# 04_MCU_ESP32.net
KiCad netlist of a schematic drawn in Altium Designer
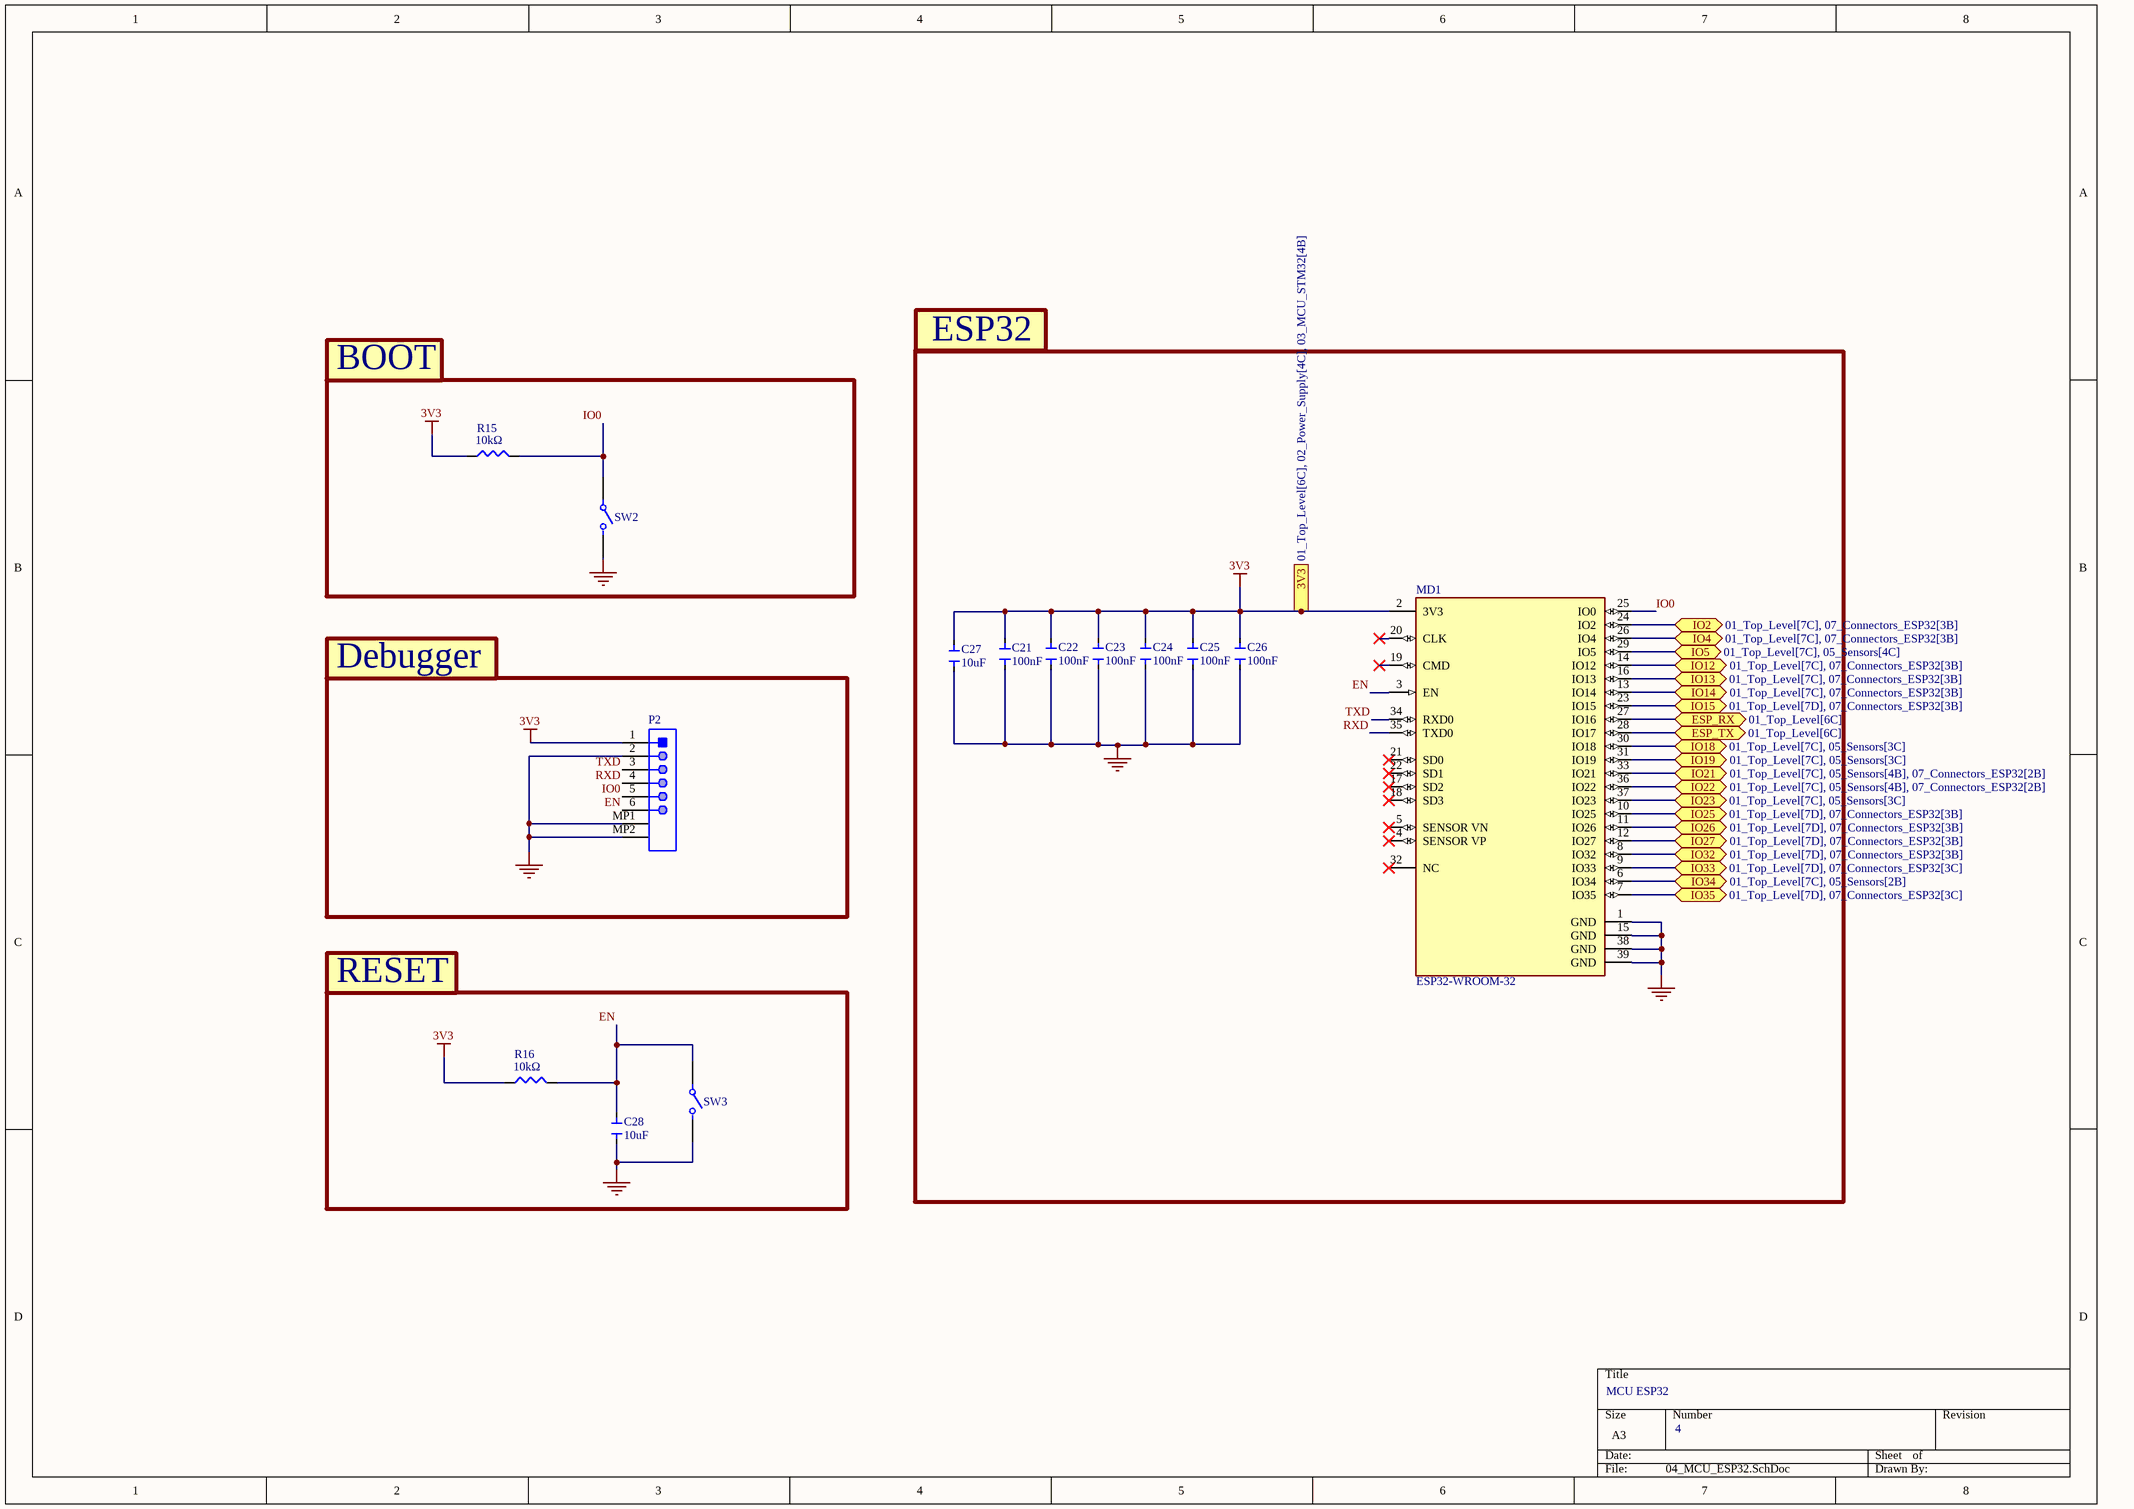
[diagram p0: 04_MCU_ESP32.SchDoc]

(export (version "E")
  (design (tool "Eeschema 10.0.6"))
  (components
    (comp (ref "C21")
      (value "100nF")
      (footprint "CAP_100nF")
      (description "CAP 100nF 50V X7R ±10% 0603 Ceramic Capacitors RoHS")
      (fields
        (field (name "MANUFACTURER") "YAGEO")
        (field (name "MANUFACTURER PART NUMBER") "CC0603KRX7R9BB104")
      )
      (libsource (lib "Components_Schlib") (part "CAP_100nF"))
    )
    (comp (ref "C22")
      (value "100nF")
      (footprint "CAP_100nF")
      (description "CAP 100nF 50V X7R ±10% 0603 Ceramic Capacitors RoHS")
      (fields
        (field (name "MANUFACTURER") "YAGEO")
        (field (name "MANUFACTURER PART NUMBER") "CC0603KRX7R9BB104")
      )
      (libsource (lib "Components_Schlib") (part "CAP_100nF"))
    )
    (comp (ref "C23")
      (value "100nF")
      (footprint "CAP_100nF")
      (description "CAP 100nF 50V X7R ±10% 0603 Ceramic Capacitors RoHS")
      (fields
        (field (name "MANUFACTURER") "YAGEO")
        (field (name "MANUFACTURER PART NUMBER") "CC0603KRX7R9BB104")
      )
      (libsource (lib "Components_Schlib") (part "CAP_100nF"))
    )
    (comp (ref "C24")
      (value "100nF")
      (footprint "CAP_100nF")
      (description "CAP 100nF 50V X7R ±10% 0603 Ceramic Capacitors RoHS")
      (fields
        (field (name "MANUFACTURER") "YAGEO")
        (field (name "MANUFACTURER PART NUMBER") "CC0603KRX7R9BB104")
      )
      (libsource (lib "Components_Schlib") (part "CAP_100nF"))
    )
    (comp (ref "C25")
      (value "100nF")
      (footprint "CAP_100nF")
      (description "CAP 100nF 50V X7R ±10% 0603 Ceramic Capacitors RoHS")
      (fields
        (field (name "MANUFACTURER") "YAGEO")
        (field (name "MANUFACTURER PART NUMBER") "CC0603KRX7R9BB104")
      )
      (libsource (lib "Components_Schlib") (part "CAP_100nF"))
    )
    (comp (ref "C26")
      (value "100nF")
      (footprint "CAP_100nF")
      (description "CAP 100nF 50V X7R ±10% 0603 Ceramic Capacitors RoHS")
      (fields
        (field (name "MANUFACTURER") "YAGEO")
        (field (name "MANUFACTURER PART NUMBER") "CC0603KRX7R9BB104")
      )
      (libsource (lib "Components_Schlib") (part "CAP_100nF"))
    )
    (comp (ref "C27")
      (value "10uF")
      (footprint "CAP_10uF")
      (description "CAP CER 10UF 10V X5R 0402")
      (fields
        (field (name "MANUFACTURER") "Samsung Electro-Mechanics")
        (field (name "MANUFACTURER PART NUMBER") "C307415")
      )
      (libsource (lib "Components_Schlib") (part "CAP_0402_10UF"))
    )
    (comp (ref "C28")
      (value "10uF")
      (footprint "CAP_10uF")
      (description "CAP CER 10UF 10V X5R 0402")
      (fields
        (field (name "MANUFACTURER") "Samsung Electro-Mechanics")
        (field (name "MANUFACTURER PART NUMBER") "C307415")
      )
      (libsource (lib "Components_Schlib") (part "CAP_0402_10UF"))
    )
    (comp (ref "MD1")
      (value "ESP32-WROOM-32")
      (footprint "FP-ESP32-WROOM-32-MFG")
      (description "RX TXRX MOD WIFI SURFACE MOUNT")
      (libsource (lib "Altium Content Vault") (part "ee866abf0b6c51247b7f5cdebf2f250"))
    )
    (comp (ref "P2")
      (value "SM06B-SRSS-TB(LF)(SN)")
      (footprint "JST-SM06B-SRSS-TB_V")
      (description "Male Header, Pitch 1 mm, 1 x 6 Position, Height 2.95 mm, -25 to 85 degC, RoHS, Tape and Reel")
      (fields (field (name "MANUFACTURER") "JST"))
      (libsource (lib "Altium Content Vault") (part "CN-1P-2M-R6"))
    )
    (comp (ref "R15")
      (value "10kΩ")
      (footprint "RES_10K")
      (description "100mW Thin Film Resistor ±0.1% ±10ppm/℃ 10kΩ 0603 Chip Resistor - Surface Mount ROHS")
      (fields
        (field (name "MANUFACTURER") "Yageo Group")
        (field (name "MANUFACTURER PART NUMBER") "RT0603BRB07169KL")
      )
      (libsource (lib "Components_Schlib") (part "RES_0603_10K"))
    )
    (comp (ref "R16")
      (value "10kΩ")
      (footprint "RES_10K")
      (description "100mW Thin Film Resistor ±0.1% ±10ppm/℃ 10kΩ 0603 Chip Resistor - Surface Mount ROHS")
      (fields
        (field (name "MANUFACTURER") "Yageo Group")
        (field (name "MANUFACTURER PART NUMBER") "RT0603BRB07169KL")
      )
      (libsource (lib "Components_Schlib") (part "RES_0603_10K"))
    )
    (comp (ref "SW2")
      (value "EVP-BD6C1A000")
      (footprint "FP-EVP-BD6C1A000-MFG")
      (description "EVP-BD6C1A000 Switch Tactile N.O. SPST Round Button J-Bend 0.05A 12VDC 3.5N SMD Automotive T/R")
      (libsource (lib "Altium Content Vault") (part "2b0b2b19372efd94fa7681498149756"))
    )
    (comp (ref "SW3")
      (value "EVP-BD6C1A000")
      (footprint "FP-EVP-BD6C1A000-MFG")
      (description "EVP-BD6C1A000 Switch Tactile N.O. SPST Round Button J-Bend 0.05A 12VDC 3.5N SMD Automotive T/R")
      (libsource (lib "Altium Content Vault") (part "2b0b2b19372efd94fa7681498149756"))
    )
  )
  (nets
    (net (code "1") (name "/EN") (class "Default")
      (node (ref "C28") (pin "1") (pinfunction "1_1") (pintype "passive"))
      (node (ref "MD1") (pin "3") (pinfunction "EN_3") (pintype "input"))
      (node (ref "P2") (pin "6") (pinfunction "6_6") (pintype "passive"))
      (node (ref "R16") (pin "2") (pinfunction "2_2") (pintype "passive"))
      (node (ref "SW3") (pin "A") (pinfunction "A_A") (pintype "passive"))
    )
    (net (code "2") (name "/ESP_RX") (class "Default")
      (node (ref "MD1") (pin "27") (pinfunction "IO16_27") (pintype "bidirectional"))
    )
    (net (code "3") (name "/ESP_TX") (class "Default")
      (node (ref "MD1") (pin "28") (pinfunction "IO17_28") (pintype "bidirectional"))
    )
    (net (code "4") (name "/IO0") (class "Default")
      (node (ref "MD1") (pin "25") (pinfunction "IO0_25") (pintype "bidirectional"))
      (node (ref "P2") (pin "5") (pinfunction "5_5") (pintype "passive"))
      (node (ref "R15") (pin "2") (pinfunction "2_2") (pintype "passive"))
      (node (ref "SW2") (pin "A") (pinfunction "A_A") (pintype "passive"))
    )
    (net (code "5") (name "/IO2") (class "Default")
      (node (ref "MD1") (pin "24") (pinfunction "IO2_24") (pintype "bidirectional"))
    )
    (net (code "6") (name "/IO4") (class "Default")
      (node (ref "MD1") (pin "26") (pinfunction "IO4_26") (pintype "bidirectional"))
    )
    (net (code "7") (name "/IO5") (class "Default")
      (node (ref "MD1") (pin "29") (pinfunction "IO5_29") (pintype "bidirectional"))
    )
    (net (code "8") (name "/IO12") (class "Default")
      (node (ref "MD1") (pin "14") (pinfunction "IO12_14") (pintype "bidirectional"))
    )
    (net (code "9") (name "/IO13") (class "Default")
      (node (ref "MD1") (pin "16") (pinfunction "IO13_16") (pintype "bidirectional"))
    )
    (net (code "10") (name "/IO14") (class "Default")
      (node (ref "MD1") (pin "13") (pinfunction "IO14_13") (pintype "bidirectional"))
    )
    (net (code "11") (name "/IO15") (class "Default")
      (node (ref "MD1") (pin "23") (pinfunction "IO15_23") (pintype "bidirectional"))
    )
    (net (code "12") (name "/IO18") (class "Default")
      (node (ref "MD1") (pin "30") (pinfunction "IO18_30") (pintype "bidirectional"))
    )
    (net (code "13") (name "/IO19") (class "Default")
      (node (ref "MD1") (pin "31") (pinfunction "IO19_31") (pintype "bidirectional"))
    )
    (net (code "14") (name "/IO21") (class "Default")
      (node (ref "MD1") (pin "33") (pinfunction "IO21_33") (pintype "bidirectional"))
    )
    (net (code "15") (name "/IO22") (class "Default")
      (node (ref "MD1") (pin "36") (pinfunction "IO22_36") (pintype "bidirectional"))
    )
    (net (code "16") (name "/IO23") (class "Default")
      (node (ref "MD1") (pin "37") (pinfunction "IO23_37") (pintype "bidirectional"))
    )
    (net (code "17") (name "/IO25") (class "Default")
      (node (ref "MD1") (pin "10") (pinfunction "IO25_10") (pintype "bidirectional"))
    )
    (net (code "18") (name "/IO26") (class "Default")
      (node (ref "MD1") (pin "11") (pinfunction "IO26_11") (pintype "bidirectional"))
    )
    (net (code "19") (name "/IO27") (class "Default")
      (node (ref "MD1") (pin "12") (pinfunction "IO27_12") (pintype "bidirectional"))
    )
    (net (code "20") (name "/IO32") (class "Default")
      (node (ref "MD1") (pin "8") (pinfunction "IO32_8") (pintype "bidirectional"))
    )
    (net (code "21") (name "/IO33") (class "Default")
      (node (ref "MD1") (pin "9") (pinfunction "IO33_9") (pintype "bidirectional"))
    )
    (net (code "22") (name "/IO34") (class "Default")
      (node (ref "MD1") (pin "6") (pinfunction "IO34_6") (pintype "bidirectional"))
    )
    (net (code "23") (name "/IO35") (class "Default")
      (node (ref "MD1") (pin "7") (pinfunction "IO35_7") (pintype "bidirectional"))
    )
    (net (code "24") (name "/RXD") (class "Default")
      (node (ref "MD1") (pin "35") (pinfunction "TXD0_35") (pintype "bidirectional"))
      (node (ref "P2") (pin "4") (pinfunction "4_4") (pintype "passive"))
    )
    (net (code "25") (name "/TXD") (class "Default")
      (node (ref "MD1") (pin "34") (pinfunction "RXD0_34") (pintype "bidirectional"))
      (node (ref "P2") (pin "3") (pinfunction "3_3") (pintype "passive"))
    )
    (net (code "26") (name "3V3") (class "Default")
      (node (ref "C21") (pin "2") (pinfunction "2_2") (pintype "passive"))
      (node (ref "C22") (pin "2") (pinfunction "2_2") (pintype "passive"))
      (node (ref "C23") (pin "2") (pinfunction "2_2") (pintype "passive"))
      (node (ref "C24") (pin "2") (pinfunction "2_2") (pintype "passive"))
      (node (ref "C25") (pin "2") (pinfunction "2_2") (pintype "passive"))
      (node (ref "C26") (pin "2") (pinfunction "2_2") (pintype "passive"))
      (node (ref "C27") (pin "2") (pinfunction "2_2") (pintype "passive"))
      (node (ref "MD1") (pin "2") (pinfunction "3V3_2") (pintype "power_in"))
      (node (ref "P2") (pin "1") (pinfunction "1_1") (pintype "passive"))
      (node (ref "R15") (pin "1") (pinfunction "1_1") (pintype "passive"))
      (node (ref "R16") (pin "1") (pinfunction "1_1") (pintype "passive"))
    )
    (net (code "27") (name "GND") (class "Default")
      (node (ref "C21") (pin "1") (pinfunction "1_1") (pintype "passive"))
      (node (ref "C22") (pin "1") (pinfunction "1_1") (pintype "passive"))
      (node (ref "C23") (pin "1") (pinfunction "1_1") (pintype "passive"))
      (node (ref "C24") (pin "1") (pinfunction "1_1") (pintype "passive"))
      (node (ref "C25") (pin "1") (pinfunction "1_1") (pintype "passive"))
      (node (ref "C26") (pin "1") (pinfunction "1_1") (pintype "passive"))
      (node (ref "C27") (pin "1") (pinfunction "1_1") (pintype "passive"))
      (node (ref "C28") (pin "2") (pinfunction "2_2") (pintype "passive"))
      (node (ref "MD1") (pin "1") (pinfunction "GND_1") (pintype "power_in"))
      (node (ref "MD1") (pin "15") (pinfunction "GND_15") (pintype "power_in"))
      (node (ref "MD1") (pin "38") (pinfunction "GND_38") (pintype "power_in"))
      (node (ref "MD1") (pin "39") (pinfunction "GND_39") (pintype "power_in"))
      (node (ref "P2") (pin "2") (pinfunction "2_2") (pintype "passive"))
      (node (ref "P2") (pin "MP1") (pinfunction "MP1_MP1") (pintype "passive"))
      (node (ref "P2") (pin "MP2") (pinfunction "MP2_MP2") (pintype "passive"))
      (node (ref "SW2") (pin "B") (pinfunction "B_B") (pintype "passive"))
      (node (ref "SW3") (pin "B") (pinfunction "B_B") (pintype "passive"))
    )
    (net (code "28") (name "unconnected-(MD1-CLK-Pad20)") (class "Default")
      (node (ref "MD1") (pin "20") (pinfunction "CLK_20") (pintype "bidirectional+no_connect"))
    )
    (net (code "29") (name "unconnected-(MD1-CMD-Pad19)") (class "Default")
      (node (ref "MD1") (pin "19") (pinfunction "CMD_19") (pintype "bidirectional+no_connect"))
    )
    (net (code "30") (name "unconnected-(MD1-NC-Pad32)") (class "Default")
      (node (ref "MD1") (pin "32") (pinfunction "NC_32") (pintype "passive+no_connect"))
    )
    (net (code "31") (name "unconnected-(MD1-SD0-Pad21)") (class "Default")
      (node (ref "MD1") (pin "21") (pinfunction "SD0_21") (pintype "bidirectional+no_connect"))
    )
    (net (code "32") (name "unconnected-(MD1-SD1-Pad22)") (class "Default")
      (node (ref "MD1") (pin "22") (pinfunction "SD1_22") (pintype "bidirectional+no_connect"))
    )
    (net (code "33") (name "unconnected-(MD1-SD2-Pad17)") (class "Default")
      (node (ref "MD1") (pin "17") (pinfunction "SD2_17") (pintype "bidirectional+no_connect"))
    )
    (net (code "34") (name "unconnected-(MD1-SD3-Pad18)") (class "Default")
      (node (ref "MD1") (pin "18") (pinfunction "SD3_18") (pintype "bidirectional+no_connect"))
    )
    (net (code "35") (name "unconnected-(MD1-SENSOR_VN-Pad5)") (class "Default")
      (node (ref "MD1") (pin "5") (pinfunction "SENSOR_VN_5") (pintype "bidirectional+no_connect"))
    )
    (net (code "36") (name "unconnected-(MD1-SENSOR_VP-Pad4)") (class "Default")
      (node (ref "MD1") (pin "4") (pinfunction "SENSOR_VP_4") (pintype "bidirectional+no_connect"))
    )
  )
)
